# ESP32Cam_Mounting_Schematic.net
KiCad netlist of a schematic drawn in Altium Designer
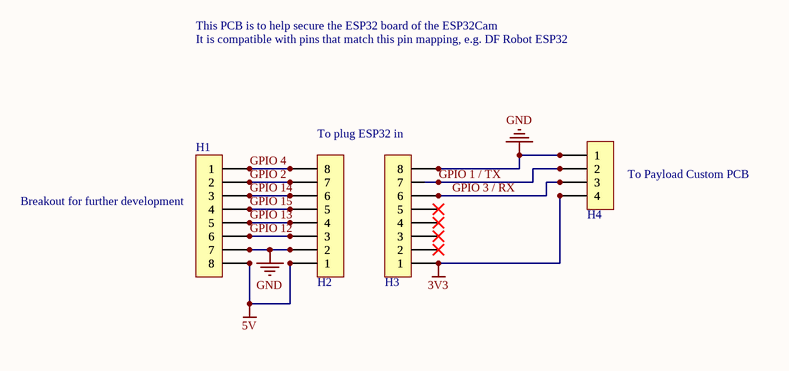
[diagram p0: ESP32Cam Mounting Schematic.SchDoc]

(export (version "E")
  (design (tool "Eeschema 10.0.6"))
  (components
    (comp (ref "H1")
      (value "8 Pin Header")
      (footprint "8 Pin Header")
      (libsource (lib "") (part "8 Pin Header_1"))
    )
    (comp (ref "H2")
      (value "8 Pin Header")
      (footprint "8 Pin Header")
      (libsource (lib "") (part "8 Pin Header_2"))
    )
    (comp (ref "H3")
      (value "8 Pin Header")
      (footprint "8 Pin Header")
      (libsource (lib "Different Header Pin Numbers") (part "8 Pin Header"))
    )
    (comp (ref "H4")
      (value "Header - 2.54mm,1x4-pin")
      (footprint "HEADER_2.54MM_1x4PIN")
      (libsource (lib "APSS Generic Components") (part "Header - 2.54mm,1x4-pin"))
    )
  )
  (nets
    (net (code "1") (name "/GPIO 1 {slash} TX") (class "Default")
      (node (ref "H3") (pin "7") (pinfunction "7_7") (pintype "passive"))
      (node (ref "H4") (pin "2") (pinfunction "2_2") (pintype "passive"))
    )
    (net (code "2") (name "/GPIO 2") (class "Default")
      (node (ref "H1") (pin "2") (pinfunction "2_2") (pintype "passive"))
      (node (ref "H2") (pin "7") (pinfunction "7_7") (pintype "passive"))
    )
    (net (code "3") (name "/GPIO 3 {slash} RX") (class "Default")
      (node (ref "H3") (pin "6") (pinfunction "6_6") (pintype "passive"))
      (node (ref "H4") (pin "3") (pinfunction "3_3") (pintype "passive"))
    )
    (net (code "4") (name "/GPIO 4") (class "Default")
      (node (ref "H1") (pin "1") (pinfunction "1_1") (pintype "passive"))
      (node (ref "H2") (pin "8") (pinfunction "8_8") (pintype "passive"))
    )
    (net (code "5") (name "/GPIO 12") (class "Default")
      (node (ref "H1") (pin "6") (pinfunction "6_6") (pintype "passive"))
      (node (ref "H2") (pin "3") (pinfunction "3_3") (pintype "passive"))
    )
    (net (code "6") (name "/GPIO 13") (class "Default")
      (node (ref "H1") (pin "5") (pinfunction "5_5") (pintype "passive"))
      (node (ref "H2") (pin "4") (pinfunction "4_4") (pintype "passive"))
    )
    (net (code "7") (name "/GPIO 14") (class "Default")
      (node (ref "H1") (pin "3") (pinfunction "3_3") (pintype "passive"))
      (node (ref "H2") (pin "6") (pinfunction "6_6") (pintype "passive"))
    )
    (net (code "8") (name "/GPIO 15") (class "Default")
      (node (ref "H1") (pin "4") (pinfunction "4_4") (pintype "passive"))
      (node (ref "H2") (pin "5") (pinfunction "5_5") (pintype "passive"))
    )
    (net (code "9") (name "3V3") (class "Default")
      (node (ref "H3") (pin "1") (pinfunction "1_1") (pintype "passive"))
      (node (ref "H4") (pin "4") (pinfunction "4_4") (pintype "passive"))
    )
    (net (code "10") (name "5V") (class "Default")
      (node (ref "H1") (pin "8") (pinfunction "8_8") (pintype "passive"))
      (node (ref "H2") (pin "1") (pinfunction "1_1") (pintype "passive"))
    )
    (net (code "11") (name "GND") (class "Default")
      (node (ref "H1") (pin "7") (pinfunction "7_7") (pintype "passive"))
      (node (ref "H2") (pin "2") (pinfunction "2_2") (pintype "passive"))
      (node (ref "H3") (pin "8") (pinfunction "8_8") (pintype "passive"))
      (node (ref "H4") (pin "1") (pinfunction "1_1") (pintype "passive"))
    )
    (net (code "12") (name "unconnected-(H3-Pad2)") (class "Default")
      (node (ref "H3") (pin "2") (pinfunction "2_2") (pintype "passive+no_connect"))
    )
    (net (code "13") (name "unconnected-(H3-Pad3)") (class "Default")
      (node (ref "H3") (pin "3") (pinfunction "3_3") (pintype "passive+no_connect"))
    )
    (net (code "14") (name "unconnected-(H3-Pad4)") (class "Default")
      (node (ref "H3") (pin "4") (pinfunction "4_4") (pintype "passive+no_connect"))
    )
    (net (code "15") (name "unconnected-(H3-Pad5)") (class "Default")
      (node (ref "H3") (pin "5") (pinfunction "5_5") (pintype "passive+no_connect"))
    )
  )
)
